# 04_MCU.net
KiCad netlist of a schematic drawn in Altium Designer
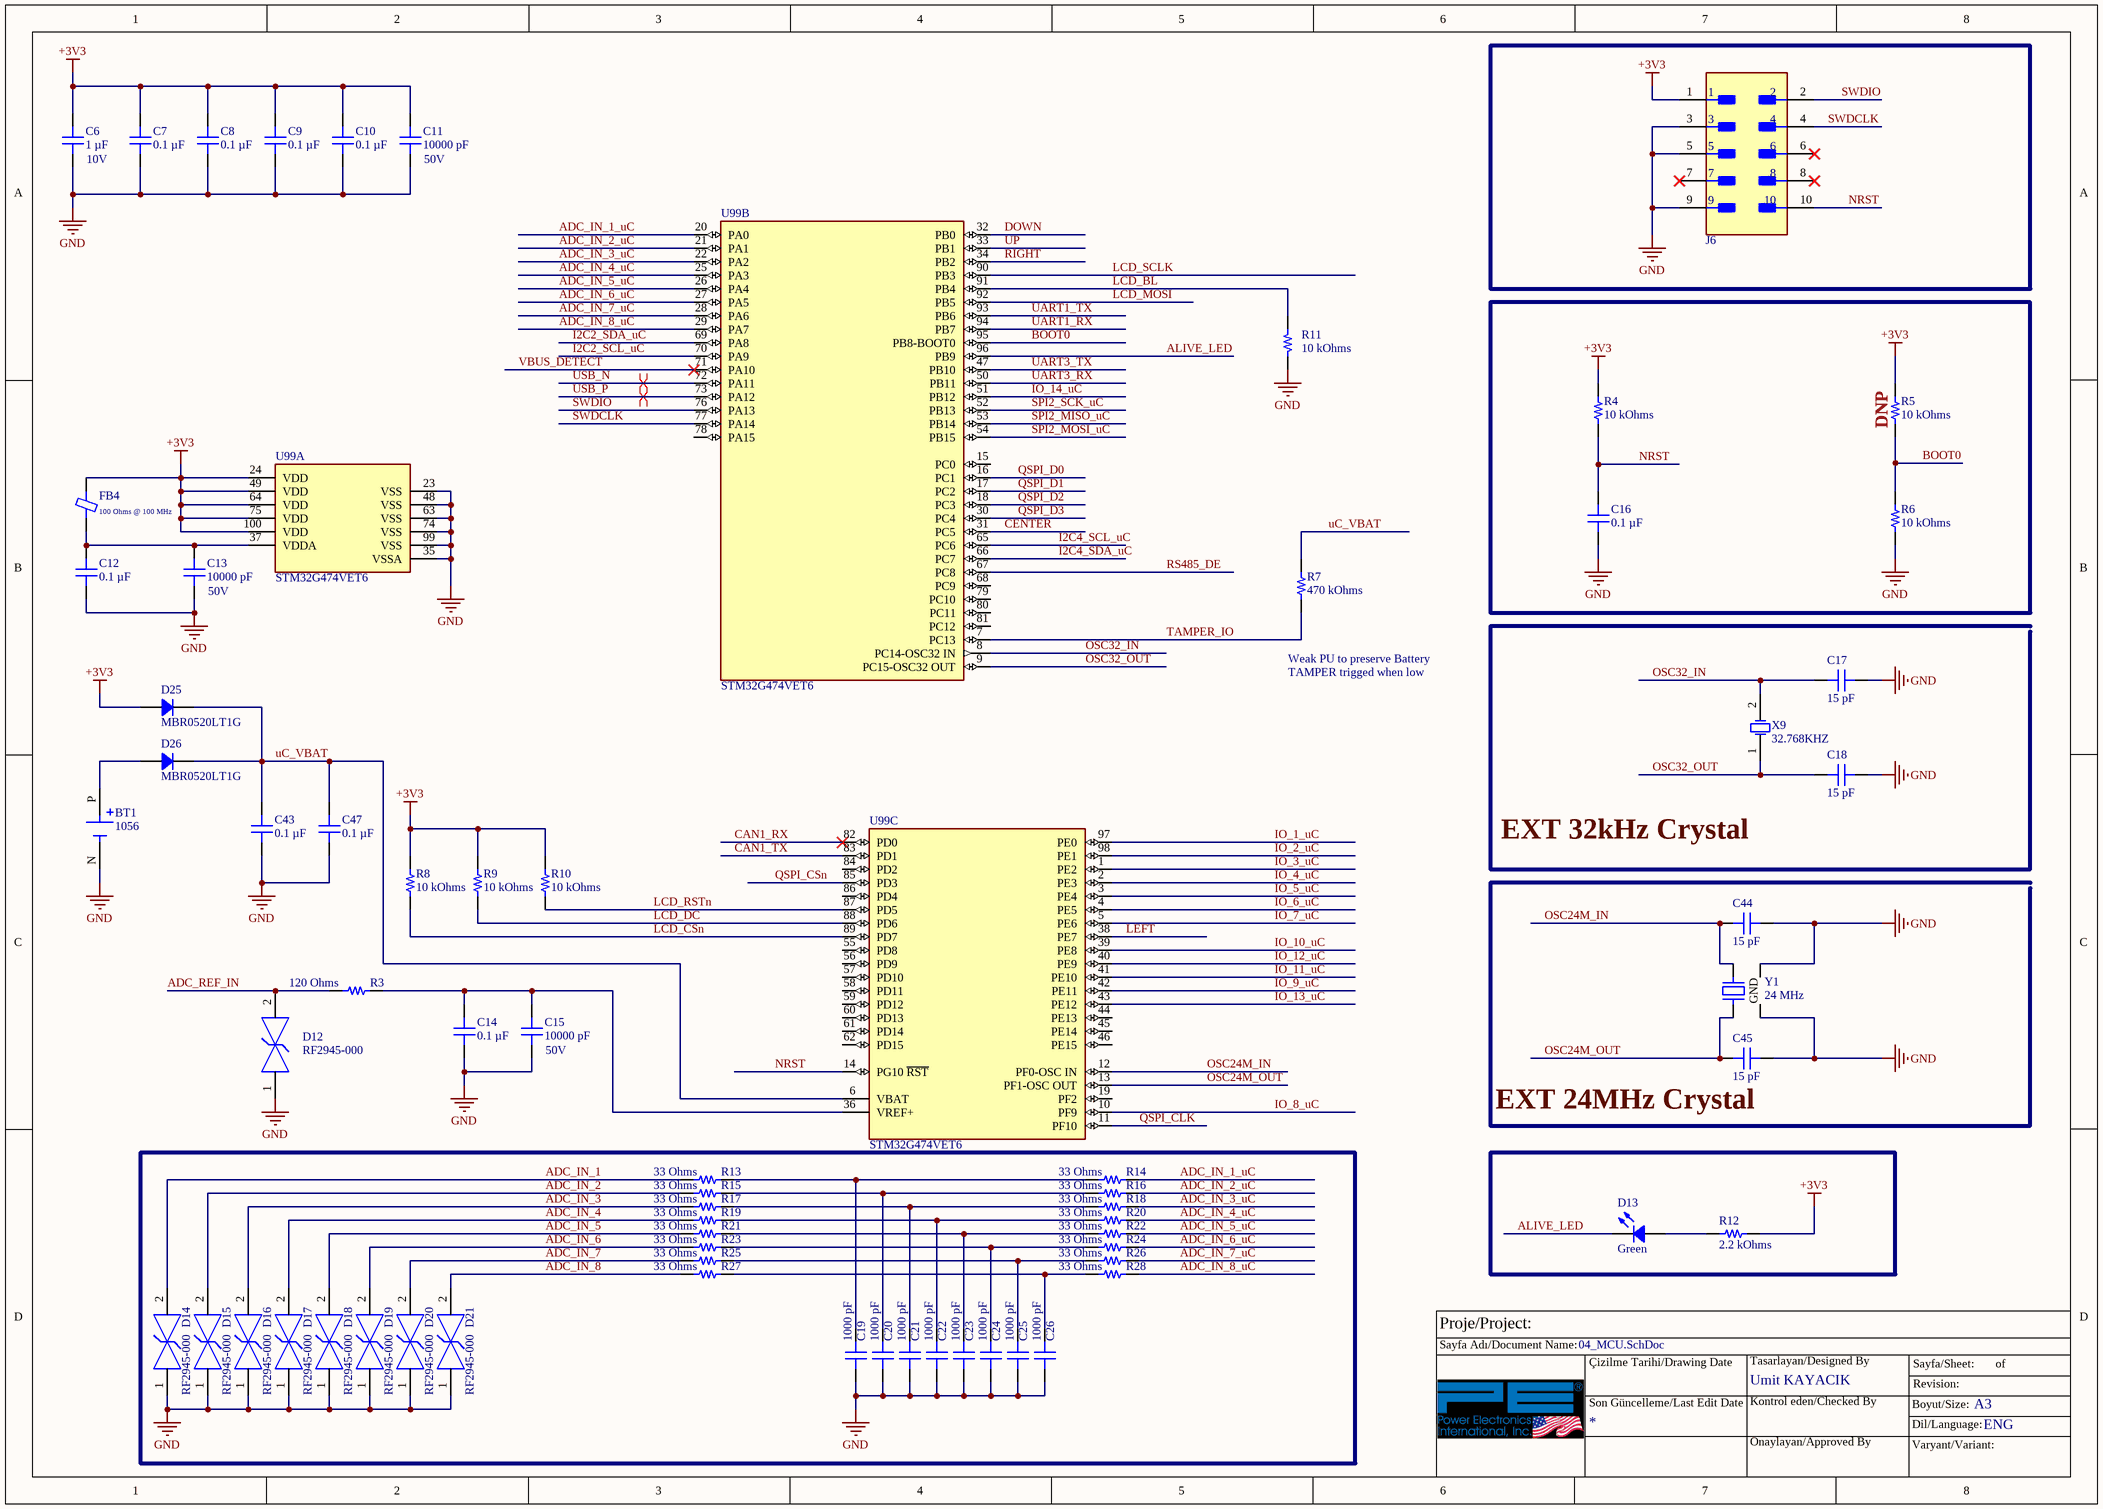
[diagram p0: 04_MCU.SchDoc]

(export (version "E")
  (design (tool "Eeschema 10.0.6"))
  (components
    (comp (ref "BT1")
      (value "1056")
      (footprint "BAT_1056")
      (description "Battery Holder, SMT, 1 Coin Cell, 12mm, Plastic, UL94V-0 ¦ Keystone Electronics 1056")
      (fields (field (name "MF") "Keystone Electronics Corp."))
      (libsource (lib "1056") (part "1056"))
    )
    (comp (ref "C6")
      (value "1 µF")
      (footprint "CAP 0402_1005")
      (description "CAP CER 1UF 10V X7S 0402")
      (fields
        (field (name "PART NUMBER") "C1005X7S1A105K050BC")
        (field (name "MANUFACTURER") "TDK Corporation")
        (field (name "VOLTAGE - RATED") "10V")
      )
      (libsource (lib "Celestial Altium Library - altium_library") (part "Capacitor"))
    )
    (comp (ref "C7")
      (value "0.1 µF")
      (footprint "MURATA GRM155 0402_1005")
      (description "CAP CER 0.1UF 50V X7R 0402")
      (fields
        (field (name "PART NUMBER") "GRM155R71H104KE14J")
        (field (name "CAPACITANCE") "0.1 µF")
        (field (name "MANUFACTURER") "Murata Electronics")
      )
      (libsource (lib "Celestial Altium Library - altium_library") (part "Capacitor"))
    )
    (comp (ref "C8")
      (value "0.1 µF")
      (footprint "MURATA GRM155 0402_1005")
      (description "CAP CER 0.1UF 50V X7R 0402")
      (fields
        (field (name "PART NUMBER") "GRM155R71H104KE14J")
        (field (name "CAPACITANCE") "0.1 µF")
        (field (name "MANUFACTURER") "Murata Electronics")
      )
      (libsource (lib "Celestial Altium Library - altium_library") (part "Capacitor"))
    )
    (comp (ref "C9")
      (value "0.1 µF")
      (footprint "MURATA GRM155 0402_1005")
      (description "CAP CER 0.1UF 50V X7R 0402")
      (fields
        (field (name "PART NUMBER") "GRM155R71H104KE14J")
        (field (name "CAPACITANCE") "0.1 µF")
        (field (name "MANUFACTURER") "Murata Electronics")
      )
      (libsource (lib "Celestial Altium Library - altium_library") (part "Capacitor"))
    )
    (comp (ref "C10")
      (value "0.1 µF")
      (footprint "MURATA GRM155 0402_1005")
      (description "CAP CER 0.1UF 50V X7R 0402")
      (fields
        (field (name "PART NUMBER") "GRM155R71H104KE14J")
        (field (name "CAPACITANCE") "0.1 µF")
        (field (name "MANUFACTURER") "Murata Electronics")
      )
      (libsource (lib "Celestial Altium Library - altium_library") (part "Capacitor"))
    )
    (comp (ref "C11")
      (value "10000 pF")
      (footprint "CAP 0402_1005")
      (description "CAP CER 10000PF 50V X7R 0402")
      (fields
        (field (name "PART NUMBER") "CC0402KRX7R9BB103")
        (field (name "MANUFACTURER") "Yageo")
        (field (name "VOLTAGE - RATED") "50V")
      )
      (libsource (lib "Celestial Altium Library - altium_library") (part "Capacitor"))
    )
    (comp (ref "C12")
      (value "0.1 µF")
      (footprint "MURATA GRM155 0402_1005")
      (description "CAP CER 0.1UF 50V X7R 0402")
      (fields
        (field (name "PART NUMBER") "GRM155R71H104KE14J")
        (field (name "CAPACITANCE") "0.1 µF")
        (field (name "MANUFACTURER") "Murata Electronics")
      )
      (libsource (lib "Celestial Altium Library - altium_library") (part "Capacitor"))
    )
    (comp (ref "C13")
      (value "10000 pF")
      (footprint "CAP 0402_1005")
      (description "CAP CER 10000PF 50V X7R 0402")
      (fields
        (field (name "PART NUMBER") "CC0402KRX7R9BB103")
        (field (name "MANUFACTURER") "Yageo")
        (field (name "VOLTAGE - RATED") "50V")
      )
      (libsource (lib "Celestial Altium Library - altium_library") (part "Capacitor"))
    )
    (comp (ref "C14")
      (value "0.1 µF")
      (footprint "MURATA GRM155 0402_1005")
      (description "CAP CER 0.1UF 50V X7R 0402")
      (fields
        (field (name "PART NUMBER") "GRM155R71H104KE14J")
        (field (name "CAPACITANCE") "0.1 µF")
        (field (name "MANUFACTURER") "Murata Electronics")
      )
      (libsource (lib "Celestial Altium Library - altium_library") (part "Capacitor"))
    )
    (comp (ref "C15")
      (value "10000 pF")
      (footprint "CAP 0402_1005")
      (description "CAP CER 10000PF 50V X7R 0402")
      (fields
        (field (name "PART NUMBER") "CC0402KRX7R9BB103")
        (field (name "MANUFACTURER") "Yageo")
        (field (name "VOLTAGE - RATED") "50V")
      )
      (libsource (lib "Celestial Altium Library - altium_library") (part "Capacitor"))
    )
    (comp (ref "C16")
      (value "0.1 µF")
      (footprint "MURATA GRM155 0402_1005")
      (description "CAP CER 0.1UF 50V X7R 0402")
      (fields
        (field (name "PART NUMBER") "GRM155R71H104KE14J")
        (field (name "CAPACITANCE") "0.1 µF")
        (field (name "MANUFACTURER") "Murata Electronics")
      )
      (libsource (lib "Celestial Altium Library - altium_library") (part "Capacitor"))
    )
    (comp (ref "C17")
      (value "15 pF")
      (footprint "CAP 0402_1005")
      (description "CAP CER 15PF 50V C0G/NPO 0402")
      (fields (field (name "PART NUMBER") "CC0402GRNPO9BN150") (field (name "MANUFACTURER") "Yageo"))
      (libsource (lib "LASER_DIAGNOSTIC_BOARD") (part "Capacitor"))
    )
    (comp (ref "C18")
      (value "15 pF")
      (footprint "CAP 0402_1005")
      (description "CAP CER 15PF 50V C0G/NPO 0402")
      (fields (field (name "PART NUMBER") "CC0402GRNPO9BN150") (field (name "MANUFACTURER") "Yageo"))
      (libsource (lib "LASER_DIAGNOSTIC_BOARD") (part "Capacitor"))
    )
    (comp (ref "C19")
      (value "1000 pF")
      (footprint "CAP 0402_1005")
      (description "CAP CER 1000PF 50V X7R 0402")
      (fields (field (name "PART NUMBER") "CC0402KRX7R9BB102") (field (name "MANUFACTURER") "Yageo"))
      (libsource (lib "Celestial Altium Library - altium_library") (part "Capacitor"))
    )
    (comp (ref "C20")
      (value "1000 pF")
      (footprint "CAP 0402_1005")
      (description "CAP CER 1000PF 50V X7R 0402")
      (fields (field (name "PART NUMBER") "CC0402KRX7R9BB102") (field (name "MANUFACTURER") "Yageo"))
      (libsource (lib "Celestial Altium Library - altium_library") (part "Capacitor"))
    )
    (comp (ref "C21")
      (value "1000 pF")
      (footprint "CAP 0402_1005")
      (description "CAP CER 1000PF 50V X7R 0402")
      (fields (field (name "PART NUMBER") "CC0402KRX7R9BB102") (field (name "MANUFACTURER") "Yageo"))
      (libsource (lib "Celestial Altium Library - altium_library") (part "Capacitor"))
    )
    (comp (ref "C22")
      (value "1000 pF")
      (footprint "CAP 0402_1005")
      (description "CAP CER 1000PF 50V X7R 0402")
      (fields (field (name "PART NUMBER") "CC0402KRX7R9BB102") (field (name "MANUFACTURER") "Yageo"))
      (libsource (lib "Celestial Altium Library - altium_library") (part "Capacitor"))
    )
    (comp (ref "C23")
      (value "1000 pF")
      (footprint "CAP 0402_1005")
      (description "CAP CER 1000PF 50V X7R 0402")
      (fields (field (name "PART NUMBER") "CC0402KRX7R9BB102") (field (name "MANUFACTURER") "Yageo"))
      (libsource (lib "Celestial Altium Library - altium_library") (part "Capacitor"))
    )
    (comp (ref "C24")
      (value "1000 pF")
      (footprint "CAP 0402_1005")
      (description "CAP CER 1000PF 50V X7R 0402")
      (fields (field (name "PART NUMBER") "CC0402KRX7R9BB102") (field (name "MANUFACTURER") "Yageo"))
      (libsource (lib "Celestial Altium Library - altium_library") (part "Capacitor"))
    )
    (comp (ref "C25")
      (value "1000 pF")
      (footprint "CAP 0402_1005")
      (description "CAP CER 1000PF 50V X7R 0402")
      (fields (field (name "PART NUMBER") "CC0402KRX7R9BB102") (field (name "MANUFACTURER") "Yageo"))
      (libsource (lib "Celestial Altium Library - altium_library") (part "Capacitor"))
    )
    (comp (ref "C26")
      (value "1000 pF")
      (footprint "CAP 0402_1005")
      (description "CAP CER 1000PF 50V X7R 0402")
      (fields (field (name "PART NUMBER") "CC0402KRX7R9BB102") (field (name "MANUFACTURER") "Yageo"))
      (libsource (lib "Celestial Altium Library - altium_library") (part "Capacitor"))
    )
    (comp (ref "C43")
      (value "0.1 µF")
      (footprint "MURATA GRM155 0402_1005")
      (description "CAP CER 0.1UF 50V X7R 0402")
      (fields
        (field (name "PART NUMBER") "GRM155R71H104KE14J")
        (field (name "CAPACITANCE") "0.1 µF")
        (field (name "MANUFACTURER") "Murata Electronics")
      )
      (libsource (lib "Celestial Altium Library - altium_library") (part "Capacitor"))
    )
    (comp (ref "C44")
      (value "15 pF")
      (footprint "CAP 0402_1005")
      (description "CAP CER 15PF 50V C0G/NPO 0402")
      (fields (field (name "PART NUMBER") "CC0402GRNPO9BN150") (field (name "MANUFACTURER") "Yageo"))
      (libsource (lib "LASER_DIAGNOSTIC_BOARD") (part "Capacitor"))
    )
    (comp (ref "C45")
      (value "15 pF")
      (footprint "CAP 0402_1005")
      (description "CAP CER 15PF 50V C0G/NPO 0402")
      (fields (field (name "PART NUMBER") "CC0402GRNPO9BN150") (field (name "MANUFACTURER") "Yageo"))
      (libsource (lib "LASER_DIAGNOSTIC_BOARD") (part "Capacitor"))
    )
    (comp (ref "C47")
      (value "0.1 µF")
      (footprint "MURATA GRM155 0402_1005")
      (description "CAP CER 0.1UF 50V X7R 0402")
      (fields
        (field (name "PART NUMBER") "GRM155R71H104KE14J")
        (field (name "CAPACITANCE") "0.1 µF")
        (field (name "MANUFACTURER") "Murata Electronics")
      )
      (libsource (lib "Celestial Altium Library - altium_library") (part "Capacitor"))
    )
    (comp (ref "D12")
      (value "RF2945-000")
      (footprint "FP-SESD0402-MFG")
      (description "TVS DIODE 7V 10V 0402")
      (fields
        (field (name "OCTOPART") "https://octopart.com/rf2945-000-littelfuse-56516902")
        (field (name "MANUFACTURER") "Littelfuse")
      )
      (libsource (lib "Altium Content Vault") (part "876f4347bf90aa6f500f43e3cd03972"))
    )
    (comp (ref "D13")
      (value "Green")
      (footprint "LED 0603_1608 GREEN")
      (description "LED GREEN 0603 SMD")
      (fields
        (field (name "PART NUMBER") "TLMP1100-GS08")
        (field (name "MANUFACTURER") "Vishay Semiconductor Opto Division")
      )
      (libsource (lib "LASER_DIAGNOSTIC_BOARD") (part "LED"))
    )
    (comp (ref "D14")
      (value "RF2945-000")
      (footprint "FP-SESD0402-MFG")
      (description "TVS DIODE 7V 10V 0402")
      (fields
        (field (name "OCTOPART") "https://octopart.com/rf2945-000-littelfuse-56516902")
        (field (name "MANUFACTURER") "Littelfuse")
      )
      (libsource (lib "Altium Content Vault") (part "876f4347bf90aa6f500f43e3cd03972"))
    )
    (comp (ref "D15")
      (value "RF2945-000")
      (footprint "FP-SESD0402-MFG")
      (description "TVS DIODE 7V 10V 0402")
      (fields
        (field (name "OCTOPART") "https://octopart.com/rf2945-000-littelfuse-56516902")
        (field (name "MANUFACTURER") "Littelfuse")
      )
      (libsource (lib "Altium Content Vault") (part "876f4347bf90aa6f500f43e3cd03972"))
    )
    (comp (ref "D16")
      (value "RF2945-000")
      (footprint "FP-SESD0402-MFG")
      (description "TVS DIODE 7V 10V 0402")
      (fields
        (field (name "OCTOPART") "https://octopart.com/rf2945-000-littelfuse-56516902")
        (field (name "MANUFACTURER") "Littelfuse")
      )
      (libsource (lib "Altium Content Vault") (part "876f4347bf90aa6f500f43e3cd03972"))
    )
    (comp (ref "D17")
      (value "RF2945-000")
      (footprint "FP-SESD0402-MFG")
      (description "TVS DIODE 7V 10V 0402")
      (fields
        (field (name "OCTOPART") "https://octopart.com/rf2945-000-littelfuse-56516902")
        (field (name "MANUFACTURER") "Littelfuse")
      )
      (libsource (lib "Altium Content Vault") (part "876f4347bf90aa6f500f43e3cd03972"))
    )
    (comp (ref "D18")
      (value "RF2945-000")
      (footprint "FP-SESD0402-MFG")
      (description "TVS DIODE 7V 10V 0402")
      (fields
        (field (name "OCTOPART") "https://octopart.com/rf2945-000-littelfuse-56516902")
        (field (name "MANUFACTURER") "Littelfuse")
      )
      (libsource (lib "Altium Content Vault") (part "876f4347bf90aa6f500f43e3cd03972"))
    )
    (comp (ref "D19")
      (value "RF2945-000")
      (footprint "FP-SESD0402-MFG")
      (description "TVS DIODE 7V 10V 0402")
      (fields
        (field (name "OCTOPART") "https://octopart.com/rf2945-000-littelfuse-56516902")
        (field (name "MANUFACTURER") "Littelfuse")
      )
      (libsource (lib "Altium Content Vault") (part "876f4347bf90aa6f500f43e3cd03972"))
    )
    (comp (ref "D20")
      (value "RF2945-000")
      (footprint "FP-SESD0402-MFG")
      (description "TVS DIODE 7V 10V 0402")
      (fields
        (field (name "OCTOPART") "https://octopart.com/rf2945-000-littelfuse-56516902")
        (field (name "MANUFACTURER") "Littelfuse")
      )
      (libsource (lib "Altium Content Vault") (part "876f4347bf90aa6f500f43e3cd03972"))
    )
    (comp (ref "D21")
      (value "RF2945-000")
      (footprint "FP-SESD0402-MFG")
      (description "TVS DIODE 7V 10V 0402")
      (fields
        (field (name "OCTOPART") "https://octopart.com/rf2945-000-littelfuse-56516902")
        (field (name "MANUFACTURER") "Littelfuse")
      )
      (libsource (lib "Altium Content Vault") (part "876f4347bf90aa6f500f43e3cd03972"))
    )
    (comp (ref "D25")
      (value "MBR0520LT1G")
      (footprint "SOD-123")
      (description "DIODE SCHOTTKY 20V 500MA SOD123")
      (fields (field (name "MANUFACTURER") "ON Semiconductor"))
      (libsource (lib "Celestial Altium Library - altium_library") (part "Diode"))
    )
    (comp (ref "D26")
      (value "MBR0520LT1G")
      (footprint "SOD-123")
      (description "DIODE SCHOTTKY 20V 500MA SOD123")
      (fields (field (name "MANUFACTURER") "ON Semiconductor"))
      (libsource (lib "Celestial Altium Library - altium_library") (part "Diode"))
    )
    (comp (ref "FB4")
      (value "100 Ohms @ 100 MHz")
      (footprint "FER 0603_1608")
      (description "FERRITE BEAD 100 OHM 0603 1LN")
      (fields (field (name "PART NUMBER") "MH1608-101Y") (field (name "MANUFACTURER") "Bourns Inc."))
      (libsource (lib "LASER_DIAGNOSTIC_BOARD") (part "Ferrite Chip"))
    )
    (comp (ref "J6")
      (value "FTSH-105-01-F-DV-K-P-TR")
      (footprint "Samtec_0_MFG")
      (description "Connector Header Surface Mount 10 position 0.050\" (1.27mm)")
      (libsource (lib "LASER_DIAGNOSTIC_BOARD") (part "FTSH-105-01-F-DV-K-P-TR"))
    )
    (comp (ref "R3")
      (value "120 Ohms")
      (footprint "YAGEO RES 0805_2012")
      (description "RES 120 OHM 1% 1/8W 0805")
      (fields (field (name "PART NUMBER") "RC0805FR-07120RL") (field (name "MANUFACTURER") "Yageo"))
      (libsource (lib "Celestial Altium Library - altium_library") (part "Resistor"))
    )
    (comp (ref "R4")
      (value "10 kOhms")
      (footprint "RES 0402_1005")
      (description "RES 10K OHM 1% 1/16W 0402")
      (fields (field (name "PART NUMBER") "RC0402FR-0710KL") (field (name "MANUFACTURER") "Yageo"))
      (libsource (lib "LASER_DIAGNOSTIC_BOARD") (part "Resistor"))
    )
    (comp (ref "R5")
      (value "10 kOhms")
      (footprint "RES 0402_1005")
      (description "RES 10K OHM 1% 1/16W 0402")
      (fields (field (name "PART NUMBER") "RC0402FR-0710KL") (field (name "MANUFACTURER") "Yageo"))
      (libsource (lib "LASER_DIAGNOSTIC_BOARD") (part "Resistor"))
    )
    (comp (ref "R6")
      (value "10 kOhms")
      (footprint "RES 0402_1005")
      (description "RES 10K OHM 1% 1/16W 0402")
      (fields (field (name "PART NUMBER") "RC0402FR-0710KL") (field (name "MANUFACTURER") "Yageo"))
      (libsource (lib "LASER_DIAGNOSTIC_BOARD") (part "Resistor"))
    )
    (comp (ref "R7")
      (value "470 kOhms")
      (footprint "YAGEO RES 0402_1005")
      (description "RES 470K OHM 1% 1/16W 0402")
      (fields (field (name "PART NUMBER") "RC0402FR-07470KL") (field (name "MANUFACTURER") "Yageo"))
      (libsource (lib "Celestial Altium Library - altium_library") (part "Resistor"))
    )
    (comp (ref "R8")
      (value "10 kOhms")
      (footprint "RES 0402_1005")
      (description "RES 10K OHM 1% 1/16W 0402")
      (fields (field (name "PART NUMBER") "RC0402FR-0710KL") (field (name "MANUFACTURER") "Yageo"))
      (libsource (lib "LASER_DIAGNOSTIC_BOARD") (part "Resistor"))
    )
    (comp (ref "R9")
      (value "10 kOhms")
      (footprint "RES 0402_1005")
      (description "RES 10K OHM 1% 1/16W 0402")
      (fields (field (name "PART NUMBER") "RC0402FR-0710KL") (field (name "MANUFACTURER") "Yageo"))
      (libsource (lib "LASER_DIAGNOSTIC_BOARD") (part "Resistor"))
    )
    (comp (ref "R10")
      (value "10 kOhms")
      (footprint "RES 0402_1005")
      (description "RES 10K OHM 1% 1/16W 0402")
      (fields (field (name "PART NUMBER") "RC0402FR-0710KL") (field (name "MANUFACTURER") "Yageo"))
      (libsource (lib "LASER_DIAGNOSTIC_BOARD") (part "Resistor"))
    )
    (comp (ref "R11")
      (value "10 kOhms")
      (footprint "RES 0402_1005")
      (description "RES 10K OHM 1% 1/16W 0402")
      (fields (field (name "PART NUMBER") "RC0402FR-0710KL") (field (name "MANUFACTURER") "Yageo"))
      (libsource (lib "LASER_DIAGNOSTIC_BOARD") (part "Resistor"))
    )
    (comp (ref "R12")
      (value "2.2 kOhms")
      (footprint "RES 0402_1005")
      (description "RES 2.2K OHM 1% 1/16W 0402")
      (fields
        (field (name "PART NUMBER") "RMCF0402FT2K20")
        (field (name "MANUFACTURER") "Stackpole Electronics Inc")
      )
      (libsource (lib "Celestial Altium Library - altium_library") (part "Resistor"))
    )
    (comp (ref "R13")
      (value "33 Ohms")
      (footprint "YAGEO RES 0402_1005")
      (description "RES 33 OHM 1% 1/16W 0402")
      (fields (field (name "PART NUMBER") "RC0402FR-0733RL") (field (name "MANUFACTURER") "Yageo"))
      (libsource (lib "Celestial Altium Library - altium_library") (part "Resistor"))
    )
    (comp (ref "R14")
      (value "33 Ohms")
      (footprint "YAGEO RES 0402_1005")
      (description "RES 33 OHM 1% 1/16W 0402")
      (fields (field (name "PART NUMBER") "RC0402FR-0733RL") (field (name "MANUFACTURER") "Yageo"))
      (libsource (lib "Celestial Altium Library - altium_library") (part "Resistor"))
    )
    (comp (ref "R15")
      (value "33 Ohms")
      (footprint "YAGEO RES 0402_1005")
      (description "RES 33 OHM 1% 1/16W 0402")
      (fields (field (name "PART NUMBER") "RC0402FR-0733RL") (field (name "MANUFACTURER") "Yageo"))
      (libsource (lib "Celestial Altium Library - altium_library") (part "Resistor"))
    )
    (comp (ref "R16")
      (value "33 Ohms")
      (footprint "YAGEO RES 0402_1005")
      (description "RES 33 OHM 1% 1/16W 0402")
      (fields (field (name "PART NUMBER") "RC0402FR-0733RL") (field (name "MANUFACTURER") "Yageo"))
      (libsource (lib "Celestial Altium Library - altium_library") (part "Resistor"))
    )
    (comp (ref "R17")
      (value "33 Ohms")
      (footprint "YAGEO RES 0402_1005")
      (description "RES 33 OHM 1% 1/16W 0402")
      (fields (field (name "PART NUMBER") "RC0402FR-0733RL") (field (name "MANUFACTURER") "Yageo"))
      (libsource (lib "Celestial Altium Library - altium_library") (part "Resistor"))
    )
    (comp (ref "R18")
      (value "33 Ohms")
      (footprint "YAGEO RES 0402_1005")
      (description "RES 33 OHM 1% 1/16W 0402")
      (fields (field (name "PART NUMBER") "RC0402FR-0733RL") (field (name "MANUFACTURER") "Yageo"))
      (libsource (lib "Celestial Altium Library - altium_library") (part "Resistor"))
    )
    (comp (ref "R19")
      (value "33 Ohms")
      (footprint "YAGEO RES 0402_1005")
      (description "RES 33 OHM 1% 1/16W 0402")
      (fields (field (name "PART NUMBER") "RC0402FR-0733RL") (field (name "MANUFACTURER") "Yageo"))
      (libsource (lib "Celestial Altium Library - altium_library") (part "Resistor"))
    )
    (comp (ref "R20")
      (value "33 Ohms")
      (footprint "YAGEO RES 0402_1005")
      (description "RES 33 OHM 1% 1/16W 0402")
      (fields (field (name "PART NUMBER") "RC0402FR-0733RL") (field (name "MANUFACTURER") "Yageo"))
      (libsource (lib "Celestial Altium Library - altium_library") (part "Resistor"))
    )
    (comp (ref "R21")
      (value "33 Ohms")
      (footprint "YAGEO RES 0402_1005")
      (description "RES 33 OHM 1% 1/16W 0402")
      (fields (field (name "PART NUMBER") "RC0402FR-0733RL") (field (name "MANUFACTURER") "Yageo"))
      (libsource (lib "Celestial Altium Library - altium_library") (part "Resistor"))
    )
    (comp (ref "R22")
      (value "33 Ohms")
      (footprint "YAGEO RES 0402_1005")
      (description "RES 33 OHM 1% 1/16W 0402")
      (fields (field (name "PART NUMBER") "RC0402FR-0733RL") (field (name "MANUFACTURER") "Yageo"))
      (libsource (lib "Celestial Altium Library - altium_library") (part "Resistor"))
    )
    (comp (ref "R23")
      (value "33 Ohms")
      (footprint "YAGEO RES 0402_1005")
      (description "RES 33 OHM 1% 1/16W 0402")
      (fields (field (name "PART NUMBER") "RC0402FR-0733RL") (field (name "MANUFACTURER") "Yageo"))
      (libsource (lib "Celestial Altium Library - altium_library") (part "Resistor"))
    )
    (comp (ref "R24")
      (value "33 Ohms")
      (footprint "YAGEO RES 0402_1005")
      (description "RES 33 OHM 1% 1/16W 0402")
      (fields (field (name "PART NUMBER") "RC0402FR-0733RL") (field (name "MANUFACTURER") "Yageo"))
      (libsource (lib "Celestial Altium Library - altium_library") (part "Resistor"))
    )
    (comp (ref "R25")
      (value "33 Ohms")
      (footprint "YAGEO RES 0402_1005")
      (description "RES 33 OHM 1% 1/16W 0402")
      (fields (field (name "PART NUMBER") "RC0402FR-0733RL") (field (name "MANUFACTURER") "Yageo"))
      (libsource (lib "Celestial Altium Library - altium_library") (part "Resistor"))
    )
    (comp (ref "R26")
      (value "33 Ohms")
      (footprint "YAGEO RES 0402_1005")
      (description "RES 33 OHM 1% 1/16W 0402")
      (fields (field (name "PART NUMBER") "RC0402FR-0733RL") (field (name "MANUFACTURER") "Yageo"))
      (libsource (lib "Celestial Altium Library - altium_library") (part "Resistor"))
    )
    (comp (ref "R27")
      (value "33 Ohms")
      (footprint "YAGEO RES 0402_1005")
      (description "RES 33 OHM 1% 1/16W 0402")
      (fields (field (name "PART NUMBER") "RC0402FR-0733RL") (field (name "MANUFACTURER") "Yageo"))
      (libsource (lib "Celestial Altium Library - altium_library") (part "Resistor"))
    )
    (comp (ref "R28")
      (value "33 Ohms")
      (footprint "YAGEO RES 0402_1005")
      (description "RES 33 OHM 1% 1/16W 0402")
      (fields (field (name "PART NUMBER") "RC0402FR-0733RL") (field (name "MANUFACTURER") "Yageo"))
      (libsource (lib "Celestial Altium Library - altium_library") (part "Resistor"))
    )
    (comp (ref "U99")
      (value "STM32G474VET6")
      (footprint "FP-LQFP100-1L-IPC_B")
      (description "IC MCU 32BIT 512KB FLASH 100LQFP")
      (libsource (lib "Altium Content Vault") (part "96fed8bfca49c3ce045f738f97905b3"))
    )
    (comp (ref "X9")
      (value "32.768KHZ")
      (footprint "CRY_ABS07")
      (description "32.768 kHz ±20ppm Crystal 12.5pF 70 kOhms 2-SMD, No Lead")
      (fields
        (field (name "MANUFACTURER PART NUMBER") "CM7V-T1A-32.768KHZ-12.5PF-20PPM-TB-QA")
        (field (name "Comment") "CRYSTAL 32.7680KHZ 12.5PF SMD")
      )
      (libsource (lib "LASER_DIAGNOSTIC_BOARD") (part "CRY_32.768KHZ"))
    )
    (comp (ref "Y1")
      (value "24 MHz")
      (footprint "EPSON TSX-3225")
      (description "CRYSTAL 24.0000MHZ 9PF SMD")
      (fields (field (name "PART NUMBER") "TSX-3225 24.0000MF20G-AC3") (field (name "MANUFACTURER") "EPSON"))
      (libsource (lib "Celestial Altium Library - altium_library") (part "Epson Crystal TSX-3225"))
    )
  )
  (nets
    (net (code "1") (name "+3V3") (class "Default")
      (node (ref "C10") (pin "2") (pinfunction "2_2") (pintype "passive"))
      (node (ref "C11") (pin "2") (pinfunction "2_2") (pintype "passive"))
      (node (ref "C6") (pin "2") (pinfunction "2_2") (pintype "passive"))
      (node (ref "C7") (pin "2") (pinfunction "2_2") (pintype "passive"))
      (node (ref "C8") (pin "2") (pinfunction "2_2") (pintype "passive"))
      (node (ref "C9") (pin "2") (pinfunction "2_2") (pintype "passive"))
      (node (ref "D25") (pin "1") (pinfunction "1_1") (pintype "passive"))
      (node (ref "FB4") (pin "2") (pinfunction "2_2") (pintype "passive"))
      (node (ref "J6") (pin "1") (pinfunction "1_1") (pintype "passive"))
      (node (ref "R10") (pin "1") (pinfunction "1_1") (pintype "passive"))
      (node (ref "R12") (pin "2") (pinfunction "2_2") (pintype "passive"))
      (node (ref "R4") (pin "1") (pinfunction "1_1") (pintype "passive"))
      (node (ref "R5") (pin "1") (pinfunction "1_1") (pintype "passive"))
      (node (ref "R8") (pin "1") (pinfunction "1_1") (pintype "passive"))
      (node (ref "R9") (pin "1") (pinfunction "1_1") (pintype "passive"))
      (node (ref "U99") (pin "100") (pinfunction "VDD_100") (pintype "power_in"))
      (node (ref "U99") (pin "24") (pinfunction "VDD_24") (pintype "power_in"))
      (node (ref "U99") (pin "49") (pinfunction "VDD_49") (pintype "power_in"))
      (node (ref "U99") (pin "64") (pinfunction "VDD_64") (pintype "power_in"))
      (node (ref "U99") (pin "75") (pinfunction "VDD_75") (pintype "power_in"))
    )
    (net (code "2") (name "/ADC_IN_1") (class "Default")
      (node (ref "D14") (pin "2") (pinfunction "2_2") (pintype "passive"))
      (node (ref "R13") (pin "1") (pinfunction "1_1") (pintype "passive"))
    )
    (net (code "3") (name "/ADC_IN_1_uC") (class "Default")
      (node (ref "R14") (pin "2") (pinfunction "2_2") (pintype "passive"))
      (node (ref "U99") (pin "20") (pinfunction "PA0_20") (pintype "bidirectional"))
    )
    (net (code "4") (name "/ADC_IN_2") (class "Default")
      (node (ref "D15") (pin "2") (pinfunction "2_2") (pintype "passive"))
      (node (ref "R15") (pin "1") (pinfunction "1_1") (pintype "passive"))
    )
    (net (code "5") (name "/ADC_IN_2_uC") (class "Default")
      (node (ref "R16") (pin "2") (pinfunction "2_2") (pintype "passive"))
      (node (ref "U99") (pin "21") (pinfunction "PA1_21") (pintype "bidirectional"))
    )
    (net (code "6") (name "/ADC_IN_3") (class "Default")
      (node (ref "D16") (pin "2") (pinfunction "2_2") (pintype "passive"))
      (node (ref "R17") (pin "1") (pinfunction "1_1") (pintype "passive"))
    )
    (net (code "7") (name "/ADC_IN_3_uC") (class "Default")
      (node (ref "R18") (pin "2") (pinfunction "2_2") (pintype "passive"))
      (node (ref "U99") (pin "22") (pinfunction "PA2_22") (pintype "bidirectional"))
    )
    (net (code "8") (name "/ADC_IN_4") (class "Default")
      (node (ref "D17") (pin "2") (pinfunction "2_2") (pintype "passive"))
      (node (ref "R19") (pin "1") (pinfunction "1_1") (pintype "passive"))
    )
    (net (code "9") (name "/ADC_IN_4_uC") (class "Default")
      (node (ref "R20") (pin "2") (pinfunction "2_2") (pintype "passive"))
      (node (ref "U99") (pin "25") (pinfunction "PA3_25") (pintype "bidirectional"))
    )
    (net (code "10") (name "/ADC_IN_5") (class "Default")
      (node (ref "D18") (pin "2") (pinfunction "2_2") (pintype "passive"))
      (node (ref "R21") (pin "1") (pinfunction "1_1") (pintype "passive"))
    )
    (net (code "11") (name "/ADC_IN_5_uC") (class "Default")
      (node (ref "R22") (pin "2") (pinfunction "2_2") (pintype "passive"))
      (node (ref "U99") (pin "26") (pinfunction "PA4_26") (pintype "bidirectional"))
    )
    (net (code "12") (name "/ADC_IN_6") (class "Default")
      (node (ref "D19") (pin "2") (pinfunction "2_2") (pintype "passive"))
      (node (ref "R23") (pin "1") (pinfunction "1_1") (pintype "passive"))
    )
    (net (code "13") (name "/ADC_IN_6_uC") (class "Default")
      (node (ref "R24") (pin "2") (pinfunction "2_2") (pintype "passive"))
      (node (ref "U99") (pin "27") (pinfunction "PA5_27") (pintype "bidirectional"))
    )
    (net (code "14") (name "/ADC_IN_7") (class "Default")
      (node (ref "D20") (pin "2") (pinfunction "2_2") (pintype "passive"))
      (node (ref "R25") (pin "1") (pinfunction "1_1") (pintype "passive"))
    )
    (net (code "15") (name "/ADC_IN_7_uC") (class "Default")
      (node (ref "R26") (pin "2") (pinfunction "2_2") (pintype "passive"))
      (node (ref "U99") (pin "28") (pinfunction "PA6_28") (pintype "bidirectional"))
    )
    (net (code "16") (name "/ADC_IN_8") (class "Default")
      (node (ref "D21") (pin "2") (pinfunction "2_2") (pintype "passive"))
      (node (ref "R27") (pin "1") (pinfunction "1_1") (pintype "passive"))
    )
    (net (code "17") (name "/ADC_IN_8_uC") (class "Default")
      (node (ref "R28") (pin "2") (pinfunction "2_2") (pintype "passive"))
      (node (ref "U99") (pin "29") (pinfunction "PA7_29") (pintype "bidirectional"))
    )
    (net (code "18") (name "/ADC_REF_IN") (class "Default")
      (node (ref "D12") (pin "2") (pinfunction "2_2") (pintype "passive"))
      (node (ref "R3") (pin "1") (pinfunction "1_1") (pintype "passive"))
    )
    (net (code "19") (name "/ALIVE_LED") (class "Default")
      (node (ref "D13") (pin "2") (pinfunction "2_2") (pintype "passive"))
      (node (ref "U99") (pin "96") (pinfunction "PB9_96") (pintype "bidirectional"))
    )
    (net (code "20") (name "/BOOT0") (class "Default")
      (node (ref "R5") (pin "2") (pinfunction "2_2") (pintype "passive"))
      (node (ref "R6") (pin "1") (pinfunction "1_1") (pintype "passive"))
      (node (ref "U99") (pin "95") (pinfunction "PB8-BOOT0_95") (pintype "bidirectional"))
    )
    (net (code "21") (name "/CAN1_RX") (class "Default")
      (node (ref "U99") (pin "82") (pinfunction "PD0_82") (pintype "bidirectional+no_connect"))
    )
    (net (code "22") (name "/CAN1_TX") (class "Default")
      (node (ref "U99") (pin "83") (pinfunction "PD1_83") (pintype "bidirectional"))
    )
    (net (code "23") (name "/CENTER") (class "Default")
      (node (ref "U99") (pin "31") (pinfunction "PC5_31") (pintype "bidirectional"))
    )
    (net (code "24") (name "/DOWN") (class "Default")
      (node (ref "U99") (pin "32") (pinfunction "PB0_32") (pintype "bidirectional"))
    )
    (net (code "25") (name "/I2C2_SCL_uC") (class "Default")
      (node (ref "U99") (pin "70") (pinfunction "PA9_70") (pintype "bidirectional"))
    )
    (net (code "26") (name "/I2C2_SDA_uC") (class "Default")
      (node (ref "U99") (pin "69") (pinfunction "PA8_69") (pintype "bidirectional"))
    )
    (net (code "27") (name "/I2C4_SCL_uC") (class "Default")
      (node (ref "U99") (pin "65") (pinfunction "PC6_65") (pintype "bidirectional"))
    )
    (net (code "28") (name "/I2C4_SDA_uC") (class "Default")
      (node (ref "U99") (pin "66") (pinfunction "PC7_66") (pintype "bidirectional"))
    )
    (net (code "29") (name "/IO_1_uC") (class "Default")
      (node (ref "U99") (pin "97") (pinfunction "PE0_97") (pintype "bidirectional"))
    )
    (net (code "30") (name "/IO_2_uC") (class "Default")
      (node (ref "U99") (pin "98") (pinfunction "PE1_98") (pintype "bidirectional"))
    )
    (net (code "31") (name "/IO_3_uC") (class "Default")
      (node (ref "U99") (pin "1") (pinfunction "PE2_1") (pintype "bidirectional"))
    )
    (net (code "32") (name "/IO_4_uC") (class "Default")
      (node (ref "U99") (pin "2") (pinfunction "PE3_2") (pintype "bidirectional"))
    )
    (net (code "33") (name "/IO_5_uC") (class "Default")
      (node (ref "U99") (pin "3") (pinfunction "PE4_3") (pintype "bidirectional"))
    )
    (net (code "34") (name "/IO_6_uC") (class "Default")
      (node (ref "U99") (pin "4") (pinfunction "PE5_4") (pintype "bidirectional"))
    )
    (net (code "35") (name "/IO_7_uC") (class "Default")
      (node (ref "U99") (pin "5") (pinfunction "PE6_5") (pintype "bidirectional"))
    )
    (net (code "36") (name "/IO_8_uC") (class "Default")
      (node (ref "U99") (pin "10") (pinfunction "PF9_10") (pintype "bidirectional"))
    )
    (net (code "37") (name "/IO_9_uC") (class "Default")
      (node (ref "U99") (pin "42") (pinfunction "PE11_42") (pintype "bidirectional"))
    )
    (net (code "38") (name "/IO_10_uC") (class "Default")
      (node (ref "U99") (pin "39") (pinfunction "PE8_39") (pintype "bidirectional"))
    )
    (net (code "39") (name "/IO_11_uC") (class "Default")
      (node (ref "U99") (pin "41") (pinfunction "PE10_41") (pintype "bidirectional"))
    )
    (net (code "40") (name "/IO_12_uC") (class "Default")
      (node (ref "U99") (pin "40") (pinfunction "PE9_40") (pintype "bidirectional"))
    )
    (net (code "41") (name "/IO_13_uC") (class "Default")
      (node (ref "U99") (pin "43") (pinfunction "PE12_43") (pintype "bidirectional"))
    )
    (net (code "42") (name "/IO_14_uC") (class "Default")
      (node (ref "U99") (pin "51") (pinfunction "PB12_51") (pintype "bidirectional"))
    )
    (net (code "43") (name "/LCD_BL") (class "Default")
      (node (ref "R11") (pin "1") (pinfunction "1_1") (pintype "passive"))
      (node (ref "U99") (pin "91") (pinfunction "PB4_91") (pintype "bidirectional"))
    )
    (net (code "44") (name "/LCD_CSn") (class "Default")
      (node (ref "R8") (pin "2") (pinfunction "2_2") (pintype "passive"))
      (node (ref "U99") (pin "89") (pinfunction "PD7_89") (pintype "bidirectional"))
    )
    (net (code "45") (name "/LCD_DC") (class "Default")
      (node (ref "R9") (pin "2") (pinfunction "2_2") (pintype "passive"))
      (node (ref "U99") (pin "88") (pinfunction "PD6_88") (pintype "bidirectional"))
    )
    (net (code "46") (name "/LCD_MOSI") (class "Default")
      (node (ref "U99") (pin "92") (pinfunction "PB5_92") (pintype "bidirectional"))
    )
    (net (code "47") (name "/LCD_RSTn") (class "Default")
      (node (ref "R10") (pin "2") (pinfunction "2_2") (pintype "passive"))
      (node (ref "U99") (pin "87") (pinfunction "PD5_87") (pintype "bidirectional"))
    )
    (net (code "48") (name "/LCD_SCLK") (class "Default")
      (node (ref "U99") (pin "90") (pinfunction "PB3_90") (pintype "bidirectional"))
    )
    (net (code "49") (name "/LEFT") (class "Default")
      (node (ref "U99") (pin "38") (pinfunction "PE7_38") (pintype "bidirectional"))
    )
    (net (code "50") (name "/NRST") (class "Default")
      (node (ref "C16") (pin "2") (pinfunction "2_2") (pintype "passive"))
      (node (ref "J6") (pin "10") (pinfunction "10_10") (pintype "passive"))
      (node (ref "R4") (pin "2") (pinfunction "2_2") (pintype "passive"))
      (node (ref "U99") (pin "14") (pinfunction "PG10_~{RST}_14") (pintype "bidirectional"))
    )
    (net (code "51") (name "/OSC24M_IN") (class "Default")
      (node (ref "C44") (pin "1") (pinfunction "1_1") (pintype "passive"))
      (node (ref "U99") (pin "12") (pinfunction "PF0-OSC_IN_12") (pintype "bidirectional"))
      (node (ref "Y1") (pin "3") (pinfunction "3_3") (pintype "passive"))
    )
    (net (code "52") (name "/OSC24M_OUT") (class "Default")
      (node (ref "C45") (pin "1") (pinfunction "1_1") (pintype "passive"))
      (node (ref "U99") (pin "13") (pinfunction "PF1-OSC_OUT_13") (pintype "bidirectional"))
      (node (ref "Y1") (pin "1") (pinfunction "1_1") (pintype "passive"))
    )
    (net (code "53") (name "/OSC32_IN") (class "Default")
      (node (ref "C17") (pin "1") (pinfunction "1_1") (pintype "passive"))
      (node (ref "U99") (pin "8") (pinfunction "PC14-OSC32_IN_8") (pintype "output"))
      (node (ref "X9") (pin "2") (pinfunction "OSC2_2") (pintype "passive"))
    )
    (net (code "54") (name "/OSC32_OUT") (class "Default")
      (node (ref "C18") (pin "1") (pinfunction "1_1") (pintype "passive"))
      (node (ref "U99") (pin "9") (pinfunction "PC15-OSC32_OUT_9") (pintype "bidirectional"))
      (node (ref "X9") (pin "1") (pinfunction "OSC1_1") (pintype "passive"))
    )
    (net (code "55") (name "/QSPI_CLK") (class "Default")
      (node (ref "U99") (pin "11") (pinfunction "PF10_11") (pintype "bidirectional"))
    )
    (net (code "56") (name "/QSPI_CSn") (class "Default")
      (node (ref "U99") (pin "85") (pinfunction "PD3_85") (pintype "bidirectional"))
    )
    (net (code "57") (name "/QSPI_D0") (class "Default")
      (node (ref "U99") (pin "16") (pinfunction "PC1_16") (pintype "bidirectional"))
    )
    (net (code "58") (name "/QSPI_D1") (class "Default")
      (node (ref "U99") (pin "17") (pinfunction "PC2_17") (pintype "bidirectional"))
    )
    (net (code "59") (name "/QSPI_D2") (class "Default")
      (node (ref "U99") (pin "18") (pinfunction "PC3_18") (pintype "bidirectional"))
    )
    (net (code "60") (name "/QSPI_D3") (class "Default")
      (node (ref "U99") (pin "30") (pinfunction "PC4_30") (pintype "bidirectional"))
    )
    (net (code "61") (name "/RIGHT") (class "Default")
      (node (ref "U99") (pin "34") (pinfunction "PB2_34") (pintype "bidirectional"))
    )
    (net (code "62") (name "/RS485_DE") (class "Default")
      (node (ref "U99") (pin "67") (pinfunction "PC8_67") (pintype "bidirectional"))
    )
    (net (code "63") (name "/SPI2_MISO_uC") (class "Default")
      (node (ref "U99") (pin "53") (pinfunction "PB14_53") (pintype "bidirectional"))
    )
    (net (code "64") (name "/SPI2_MOSI_uC") (class "Default")
      (node (ref "U99") (pin "54") (pinfunction "PB15_54") (pintype "bidirectional"))
    )
    (net (code "65") (name "/SPI2_SCK_uC") (class "Default")
      (node (ref "U99") (pin "52") (pinfunction "PB13_52") (pintype "bidirectional"))
    )
    (net (code "66") (name "/SWDCLK") (class "Default")
      (node (ref "J6") (pin "4") (pinfunction "4_4") (pintype "passive"))
      (node (ref "U99") (pin "77") (pinfunction "PA14_77") (pintype "bidirectional"))
    )
    (net (code "67") (name "/SWDIO") (class "Default")
      (node (ref "J6") (pin "2") (pinfunction "2_2") (pintype "passive"))
      (node (ref "U99") (pin "76") (pinfunction "PA13_76") (pintype "bidirectional"))
    )
    (net (code "68") (name "/TAMPER_IO") (class "Default")
      (node (ref "R7") (pin "1") (pinfunction "1_1") (pintype "passive"))
      (node (ref "U99") (pin "7") (pinfunction "PC13_7") (pintype "bidirectional"))
    )
    (net (code "69") (name "/UART1_RX") (class "Default")
      (node (ref "U99") (pin "94") (pinfunction "PB7_94") (pintype "bidirectional"))
    )
    (net (code "70") (name "/UART1_TX") (class "Default")
      (node (ref "U99") (pin "93") (pinfunction "PB6_93") (pintype "bidirectional"))
    )
    (net (code "71") (name "/UART3_RX") (class "Default")
      (node (ref "U99") (pin "50") (pinfunction "PB11_50") (pintype "bidirectional"))
    )
    (net (code "72") (name "/UART3_TX") (class "Default")
      (node (ref "U99") (pin "47") (pinfunction "PB10_47") (pintype "bidirectional"))
    )
    (net (code "73") (name "/UP") (class "Default")
      (node (ref "U99") (pin "33") (pinfunction "PB1_33") (pintype "bidirectional"))
    )
    (net (code "74") (name "/USB_N") (class "Default")
      (node (ref "U99") (pin "72") (pinfunction "PA11_72") (pintype "bidirectional"))
    )
    (net (code "75") (name "/USB_P") (class "Default")
      (node (ref "U99") (pin "73") (pinfunction "PA12_73") (pintype "bidirectional"))
    )
    (net (code "76") (name "/VBUS_DETECT") (class "Default")
      (node (ref "U99") (pin "71") (pinfunction "PA10_71") (pintype "bidirectional+no_connect"))
    )
    (net (code "77") (name "/uC_VBAT") (class "Default")
      (node (ref "C43") (pin "2") (pinfunction "2_2") (pintype "passive"))
      (node (ref "C47") (pin "2") (pinfunction "2_2") (pintype "passive"))
      (node (ref "D25") (pin "2") (pinfunction "2_2") (pintype "passive"))
      (node (ref "D26") (pin "2") (pinfunction "2_2") (pintype "passive"))
      (node (ref "R7") (pin "2") (pinfunction "2_2") (pintype "passive"))
      (node (ref "U99") (pin "6") (pinfunction "VBAT_6") (pintype "power_in"))
    )
    (net (code "78") (name "GND") (class "Default")
      (node (ref "BT1") (pin "N") (pinfunction "NEG_N") (pintype "passive"))
      (node (ref "C10") (pin "1") (pinfunction "1_1") (pintype "passive"))
      (node (ref "C11") (pin "1") (pinfunction "1_1") (pintype "passive"))
      (node (ref "C12") (pin "1") (pinfunction "1_1") (pintype "passive"))
      (node (ref "C13") (pin "1") (pinfunction "1_1") (pintype "passive"))
      (node (ref "C14") (pin "1") (pinfunction "1_1") (pintype "passive"))
      (node (ref "C15") (pin "1") (pinfunction "1_1") (pintype "passive"))
      (node (ref "C16") (pin "1") (pinfunction "1_1") (pintype "passive"))
      (node (ref "C17") (pin "2") (pinfunction "2_2") (pintype "passive"))
      (node (ref "C18") (pin "2") (pinfunction "2_2") (pintype "passive"))
      (node (ref "C19") (pin "1") (pinfunction "1_1") (pintype "passive"))
      (node (ref "C20") (pin "1") (pinfunction "1_1") (pintype "passive"))
      (node (ref "C21") (pin "1") (pinfunction "1_1") (pintype "passive"))
      (node (ref "C22") (pin "1") (pinfunction "1_1") (pintype "passive"))
      (node (ref "C23") (pin "1") (pinfunction "1_1") (pintype "passive"))
      (node (ref "C24") (pin "1") (pinfunction "1_1") (pintype "passive"))
      (node (ref "C25") (pin "1") (pinfunction "1_1") (pintype "passive"))
      (node (ref "C26") (pin "1") (pinfunction "1_1") (pintype "passive"))
      (node (ref "C43") (pin "1") (pinfunction "1_1") (pintype "passive"))
      (node (ref "C44") (pin "2") (pinfunction "2_2") (pintype "passive"))
      (node (ref "C45") (pin "2") (pinfunction "2_2") (pintype "passive"))
      (node (ref "C47") (pin "1") (pinfunction "1_1") (pintype "passive"))
      (node (ref "C6") (pin "1") (pinfunction "1_1") (pintype "passive"))
      (node (ref "C7") (pin "1") (pinfunction "1_1") (pintype "passive"))
      (node (ref "C8") (pin "1") (pinfunction "1_1") (pintype "passive"))
      (node (ref "C9") (pin "1") (pinfunction "1_1") (pintype "passive"))
      (node (ref "D12") (pin "1") (pinfunction "1_1") (pintype "passive"))
      (node (ref "D14") (pin "1") (pinfunction "1_1") (pintype "passive"))
      (node (ref "D15") (pin "1") (pinfunction "1_1") (pintype "passive"))
      (node (ref "D16") (pin "1") (pinfunction "1_1") (pintype "passive"))
      (node (ref "D17") (pin "1") (pinfunction "1_1") (pintype "passive"))
      (node (ref "D18") (pin "1") (pinfunction "1_1") (pintype "passive"))
      (node (ref "D19") (pin "1") (pinfunction "1_1") (pintype "passive"))
      (node (ref "D20") (pin "1") (pinfunction "1_1") (pintype "passive"))
      (node (ref "D21") (pin "1") (pinfunction "1_1") (pintype "passive"))
      (node (ref "J6") (pin "3") (pinfunction "3_3") (pintype "passive"))
      (node (ref "J6") (pin "5") (pinfunction "5_5") (pintype "passive"))
      (node (ref "J6") (pin "9") (pinfunction "9_9") (pintype "passive"))
      (node (ref "R11") (pin "2") (pinfunction "2_2") (pintype "passive"))
      (node (ref "R6") (pin "2") (pinfunction "2_2") (pintype "passive"))
      (node (ref "U99") (pin "23") (pinfunction "VSS_23") (pintype "power_in"))
      (node (ref "U99") (pin "35") (pinfunction "VSSA_35") (pintype "power_in"))
      (node (ref "U99") (pin "48") (pinfunction "VSS_48") (pintype "power_in"))
      (node (ref "U99") (pin "63") (pinfunction "VSS_63") (pintype "power_in"))
      (node (ref "U99") (pin "74") (pinfunction "VSS_74") (pintype "power_in"))
      (node (ref "U99") (pin "99") (pinfunction "VSS_99") (pintype "power_in"))
      (node (ref "Y1") (pin "2") (pinfunction "GND_2") (pintype "passive"))
      (node (ref "Y1") (pin "4") (pinfunction "GND_4") (pintype "passive"))
    )
    (net (code "79") (name "Net-(BT1-POS)") (class "Default")
      (node (ref "BT1") (pin "P") (pinfunction "POS_P") (pintype "passive"))
      (node (ref "D26") (pin "1") (pinfunction "1_1") (pintype "passive"))
    )
    (net (code "80") (name "Net-(C19-Pad2)") (class "Default")
      (node (ref "C19") (pin "2") (pinfunction "2_2") (pintype "passive"))
      (node (ref "R13") (pin "2") (pinfunction "2_2") (pintype "passive"))
      (node (ref "R14") (pin "1") (pinfunction "1_1") (pintype "passive"))
    )
    (net (code "81") (name "Net-(C20-Pad2)") (class "Default")
      (node (ref "C20") (pin "2") (pinfunction "2_2") (pintype "passive"))
      (node (ref "R15") (pin "2") (pinfunction "2_2") (pintype "passive"))
      (node (ref "R16") (pin "1") (pinfunction "1_1") (pintype "passive"))
    )
    (net (code "82") (name "Net-(C21-Pad2)") (class "Default")
      (node (ref "C21") (pin "2") (pinfunction "2_2") (pintype "passive"))
      (node (ref "R17") (pin "2") (pinfunction "2_2") (pintype "passive"))
      (node (ref "R18") (pin "1") (pinfunction "1_1") (pintype "passive"))
    )
    (net (code "83") (name "Net-(C22-Pad2)") (class "Default")
      (node (ref "C22") (pin "2") (pinfunction "2_2") (pintype "passive"))
      (node (ref "R19") (pin "2") (pinfunction "2_2") (pintype "passive"))
      (node (ref "R20") (pin "1") (pinfunction "1_1") (pintype "passive"))
    )
    (net (code "84") (name "Net-(C23-Pad2)") (class "Default")
      (node (ref "C23") (pin "2") (pinfunction "2_2") (pintype "passive"))
      (node (ref "R21") (pin "2") (pinfunction "2_2") (pintype "passive"))
      (node (ref "R22") (pin "1") (pinfunction "1_1") (pintype "passive"))
    )
    (net (code "85") (name "Net-(C24-Pad2)") (class "Default")
      (node (ref "C24") (pin "2") (pinfunction "2_2") (pintype "passive"))
      (node (ref "R23") (pin "2") (pinfunction "2_2") (pintype "passive"))
      (node (ref "R24") (pin "1") (pinfunction "1_1") (pintype "passive"))
    )
    (net (code "86") (name "Net-(C25-Pad2)") (class "Default")
      (node (ref "C25") (pin "2") (pinfunction "2_2") (pintype "passive"))
      (node (ref "R25") (pin "2") (pinfunction "2_2") (pintype "passive"))
      (node (ref "R26") (pin "1") (pinfunction "1_1") (pintype "passive"))
    )
    (net (code "87") (name "Net-(C26-Pad2)") (class "Default")
      (node (ref "C26") (pin "2") (pinfunction "2_2") (pintype "passive"))
      (node (ref "R27") (pin "2") (pinfunction "2_2") (pintype "passive"))
      (node (ref "R28") (pin "1") (pinfunction "1_1") (pintype "passive"))
    )
    (net (code "88") (name "Net-(D13-Pad1)") (class "Default")
      (node (ref "D13") (pin "1") (pinfunction "1_1") (pintype "passive"))
      (node (ref "R12") (pin "1") (pinfunction "1_1") (pintype "passive"))
    )
    (net (code "89") (name "Net-(U99A-VDDA)") (class "Default")
      (node (ref "C12") (pin "2") (pinfunction "2_2") (pintype "passive"))
      (node (ref "C13") (pin "2") (pinfunction "2_2") (pintype "passive"))
      (node (ref "FB4") (pin "1") (pinfunction "1_1") (pintype "passive"))
      (node (ref "U99") (pin "37") (pinfunction "VDDA_37") (pintype "power_in"))
    )
    (net (code "90") (name "Net-(U99C-VREF+)") (class "Default")
      (node (ref "C14") (pin "2") (pinfunction "2_2") (pintype "passive"))
      (node (ref "C15") (pin "2") (pinfunction "2_2") (pintype "passive"))
      (node (ref "R3") (pin "2") (pinfunction "2_2") (pintype "passive"))
      (node (ref "U99") (pin "36") (pinfunction "VREF+_36") (pintype "power_in"))
    )
    (net (code "91") (name "unconnected-(J6-Pad6)") (class "Default")
      (node (ref "J6") (pin "6") (pinfunction "6_6") (pintype "passive+no_connect"))
    )
    (net (code "92") (name "unconnected-(J6-Pad7)") (class "Default")
      (node (ref "J6") (pin "7") (pinfunction "7_7") (pintype "passive+no_connect"))
    )
    (net (code "93") (name "unconnected-(J6-Pad8)") (class "Default")
      (node (ref "J6") (pin "8") (pinfunction "8_8") (pintype "passive+no_connect"))
    )
    (net (code "94") (name "unconnected-(U99B-PA15-Pad78)") (class "Default")
      (node (ref "U99") (pin "78") (pinfunction "PA15_78") (pintype "bidirectional"))
    )
    (net (code "95") (name "unconnected-(U99B-PC0-Pad15)") (class "Default")
      (node (ref "U99") (pin "15") (pinfunction "PC0_15") (pintype "bidirectional"))
    )
    (net (code "96") (name "unconnected-(U99B-PC9-Pad68)") (class "Default")
      (node (ref "U99") (pin "68") (pinfunction "PC9_68") (pintype "bidirectional"))
    )
    (net (code "97") (name "unconnected-(U99B-PC10-Pad79)") (class "Default")
      (node (ref "U99") (pin "79") (pinfunction "PC10_79") (pintype "bidirectional"))
    )
    (net (code "98") (name "unconnected-(U99B-PC11-Pad80)") (class "Default")
      (node (ref "U99") (pin "80") (pinfunction "PC11_80") (pintype "bidirectional"))
    )
    (net (code "99") (name "unconnected-(U99B-PC12-Pad81)") (class "Default")
      (node (ref "U99") (pin "81") (pinfunction "PC12_81") (pintype "bidirectional"))
    )
    (net (code "100") (name "unconnected-(U99C-PD2-Pad84)") (class "Default")
      (node (ref "U99") (pin "84") (pinfunction "PD2_84") (pintype "bidirectional"))
    )
    (net (code "101") (name "unconnected-(U99C-PD4-Pad86)") (class "Default")
      (node (ref "U99") (pin "86") (pinfunction "PD4_86") (pintype "bidirectional"))
    )
    (net (code "102") (name "unconnected-(U99C-PD8-Pad55)") (class "Default")
      (node (ref "U99") (pin "55") (pinfunction "PD8_55") (pintype "bidirectional"))
    )
    (net (code "103") (name "unconnected-(U99C-PD9-Pad56)") (class "Default")
      (node (ref "U99") (pin "56") (pinfunction "PD9_56") (pintype "bidirectional"))
    )
    (net (code "104") (name "unconnected-(U99C-PD10-Pad57)") (class "Default")
      (node (ref "U99") (pin "57") (pinfunction "PD10_57") (pintype "bidirectional"))
    )
    (net (code "105") (name "unconnected-(U99C-PD11-Pad58)") (class "Default")
      (node (ref "U99") (pin "58") (pinfunction "PD11_58") (pintype "bidirectional"))
    )
    (net (code "106") (name "unconnected-(U99C-PD12-Pad59)") (class "Default")
      (node (ref "U99") (pin "59") (pinfunction "PD12_59") (pintype "bidirectional"))
    )
    (net (code "107") (name "unconnected-(U99C-PD13-Pad60)") (class "Default")
      (node (ref "U99") (pin "60") (pinfunction "PD13_60") (pintype "bidirectional"))
    )
    (net (code "108") (name "unconnected-(U99C-PD14-Pad61)") (class "Default")
      (node (ref "U99") (pin "61") (pinfunction "PD14_61") (pintype "bidirectional"))
    )
    (net (code "109") (name "unconnected-(U99C-PD15-Pad62)") (class "Default")
      (node (ref "U99") (pin "62") (pinfunction "PD15_62") (pintype "bidirectional"))
    )
    (net (code "110") (name "unconnected-(U99C-PE13-Pad44)") (class "Default")
      (node (ref "U99") (pin "44") (pinfunction "PE13_44") (pintype "bidirectional"))
    )
    (net (code "111") (name "unconnected-(U99C-PE14-Pad45)") (class "Default")
      (node (ref "U99") (pin "45") (pinfunction "PE14_45") (pintype "bidirectional"))
    )
    (net (code "112") (name "unconnected-(U99C-PE15-Pad46)") (class "Default")
      (node (ref "U99") (pin "46") (pinfunction "PE15_46") (pintype "bidirectional"))
    )
    (net (code "113") (name "unconnected-(U99C-PF2-Pad19)") (class "Default")
      (node (ref "U99") (pin "19") (pinfunction "PF2_19") (pintype "bidirectional"))
    )
  )
)
